# APRS_TRacker_2.net
KiCad netlist of a schematic drawn in EAGLE
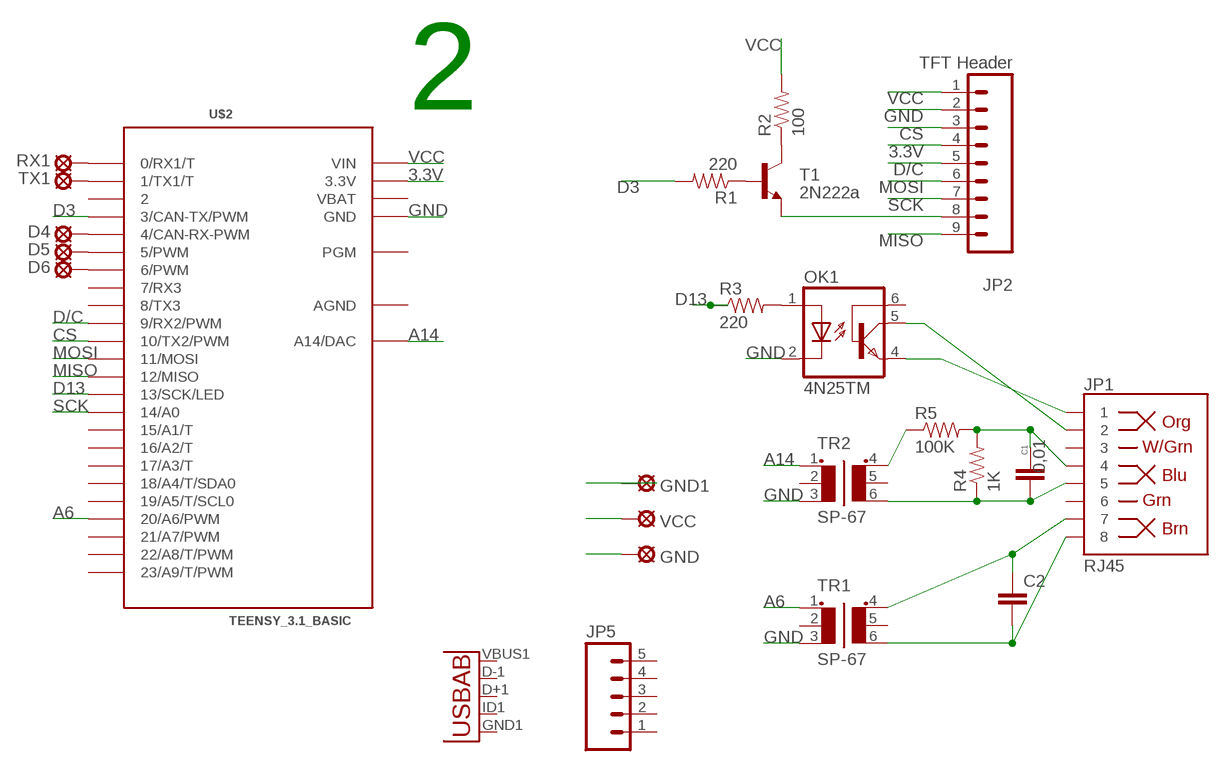
[diagram p0: schematic, sheet 1]

(export (version "E")
  (design (tool "Eeschema 10.0.6"))
  (components
    (comp (ref "C1")
      (value "0,01")
      (footprint "eagle-import:CAP-PTH-SMALL2")
      (libsource (lib "eagle-import") (part "CAPPTH2"))
    )
    (comp (ref "C2")
      (value "CAPPTH2")
      (footprint "eagle-import:CAP-PTH-SMALL2")
      (libsource (lib "eagle-import") (part "CAPPTH2"))
    )
    (comp (ref "D4")
      (value "LSP10")
      (footprint "eagle-import:LSP10")
      (libsource (lib "eagle-import") (part "LSP10"))
    )
    (comp (ref "D5")
      (value "LSP10")
      (footprint "eagle-import:LSP10")
      (libsource (lib "eagle-import") (part "LSP10"))
    )
    (comp (ref "D6")
      (value "LSP10")
      (footprint "eagle-import:LSP10")
      (libsource (lib "eagle-import") (part "LSP10"))
    )
    (comp (ref "GND")
      (value "LSP10")
      (footprint "eagle-import:LSP10")
      (libsource (lib "eagle-import") (part "LSP10"))
    )
    (comp (ref "GND1")
      (value "LSP10")
      (footprint "eagle-import:LSP10")
      (libsource (lib "eagle-import") (part "LSP10"))
    )
    (comp (ref "JP1")
      (value "RJ45")
      (footprint "eagle-import:RJ45-8")
      (libsource (lib "eagle-import") (part "RJ45-8PTH"))
    )
    (comp (ref "JP2")
      (value "TFT Header")
      (footprint "eagle-import:1X09")
      (libsource (lib "eagle-import") (part "M09"))
    )
    (comp (ref "JP5")
      (value "M05PTH")
      (footprint "eagle-import:1X05")
      (libsource (lib "eagle-import") (part "M05PTH"))
    )
    (comp (ref "OK1")
      (value "4N25TM")
      (footprint "eagle-import:DIL6-04")
      (libsource (lib "eagle-import") (part "4N?MT25"))
    )
    (comp (ref "R1")
      (value "220")
      (footprint "eagle-import:AXIAL-0.4")
      (libsource (lib "eagle-import") (part "RESISTORPTH-1/4W"))
    )
    (comp (ref "R2")
      (value "100")
      (footprint "eagle-import:AXIAL-0.4")
      (libsource (lib "eagle-import") (part "RESISTORPTH-1/4W"))
    )
    (comp (ref "R3")
      (value "220")
      (footprint "eagle-import:AXIAL-0.4")
      (libsource (lib "eagle-import") (part "RESISTORPTH-1/4W"))
    )
    (comp (ref "R4")
      (value "1K")
      (footprint "eagle-import:AXIAL-0.4")
      (libsource (lib "eagle-import") (part "RESISTORPTH-1/4W"))
    )
    (comp (ref "R5")
      (value "100K")
      (footprint "eagle-import:AXIAL-0.4")
      (libsource (lib "eagle-import") (part "RESISTORPTH-1/4W"))
    )
    (comp (ref "RX1")
      (value "LSP10")
      (footprint "eagle-import:LSP10")
      (libsource (lib "eagle-import") (part "LSP10"))
    )
    (comp (ref "T1")
      (value "2N222a")
      (footprint "eagle-import:TO-92")
      (libsource (lib "eagle-import") (part "TRANSISTOR_NPNP2N2222A"))
    )
    (comp (ref "TR1")
      (value "SP-67")
      (footprint "eagle-import:SP-67")
      (libsource (lib "eagle-import") (part "SP-67"))
    )
    (comp (ref "TR2")
      (value "SP-67")
      (footprint "eagle-import:SP-67")
      (libsource (lib "eagle-import") (part "SP-67"))
    )
    (comp (ref "TX1")
      (value "LSP10")
      (footprint "eagle-import:LSP10")
      (libsource (lib "eagle-import") (part "LSP10"))
    )
    (comp (ref "U$2")
      (value "TEENSY_3.1_BASIC")
      (footprint "eagle-import:TEENSY_3.1_BASIC")
      (libsource (lib "eagle-import") (part "TEENSY_3.1_BASIC"))
    )
    (comp (ref "U$4")
      (value "USB-AB\"\"")
      (footprint "eagle-import:USB-AB-MICRO-SMD_V02_BOSS")
      (libsource (lib "eagle-import") (part "USB-AB{dblquote}{dblquote}"))
    )
    (comp (ref "VCC")
      (value "LSP10")
      (footprint "eagle-import:LSP10")
      (libsource (lib "eagle-import") (part "LSP10"))
    )
  )
  (nets
    (net (code "1") (name "/3.3V") (class "Default")
      (node (ref "JP2") (pin "4") (pinfunction "4_4") (pintype "passive"))
      (node (ref "U$2") (pin "3.3V") (pinfunction "3.3V_3.3V") (pintype "power_in"))
      (node (ref "U$2") (pin "3.3V1") (pinfunction "3.3V_3.3V1") (pintype "power_in"))
    )
    (net (code "2") (name "/A6") (class "Default")
      (node (ref "TR1") (pin "1") (pinfunction "1_1") (pintype "passive"))
      (node (ref "U$2") (pin "20/A6") (pinfunction "20/A6/PWM_20/A6") (pintype "bidirectional"))
    )
    (net (code "3") (name "/A14") (class "Default")
      (node (ref "TR2") (pin "1") (pinfunction "1_1") (pintype "passive"))
      (node (ref "U$2") (pin "A14") (pinfunction "A14/DAC_A14") (pintype "bidirectional"))
    )
    (net (code "4") (name "/AGND") (class "Default")
      (node (ref "U$2") (pin "AGND") (pinfunction "AGND_AGND") (pintype "power_in"))
    )
    (net (code "5") (name "/CS") (class "Default")
      (node (ref "JP2") (pin "3") (pinfunction "3_3") (pintype "passive"))
      (node (ref "U$2") (pin "10") (pinfunction "10/TX2/PWM_10") (pintype "bidirectional"))
    )
    (net (code "6") (name "/D3") (class "Default")
      (node (ref "R1") (pin "P$2") (pinfunction "2_P$2") (pintype "passive"))
      (node (ref "U$2") (pin "3") (pinfunction "3/CAN-TX/PWM_3") (pintype "bidirectional"))
    )
    (net (code "7") (name "/D13") (class "Default")
      (node (ref "R3") (pin "P$1") (pinfunction "1_P$1") (pintype "passive"))
      (node (ref "U$2") (pin "13") (pinfunction "13/SCK/LED_13") (pintype "bidirectional"))
    )
    (net (code "8") (name "/D{slash}C") (class "Default")
      (node (ref "JP2") (pin "5") (pinfunction "5_5") (pintype "passive"))
      (node (ref "U$2") (pin "9") (pinfunction "9/RX2/PWM_9") (pintype "bidirectional"))
    )
    (net (code "9") (name "/GND") (class "Default")
      (node (ref "GND") (pin "MP") (pinfunction "MP_MP") (pintype "passive"))
      (node (ref "GND1") (pin "MP") (pinfunction "MP_MP") (pintype "passive"))
      (node (ref "JP2") (pin "2") (pinfunction "2_2") (pintype "passive"))
      (node (ref "OK1") (pin "2") (pinfunction "C_2") (pintype "passive"))
      (node (ref "TR1") (pin "3") (pinfunction "3_3") (pintype "passive"))
      (node (ref "TR2") (pin "3") (pinfunction "3_3") (pintype "passive"))
      (node (ref "U$2") (pin "GND") (pinfunction "GND_GND") (pintype "power_in"))
      (node (ref "U$2") (pin "GND1") (pinfunction "GND_GND1") (pintype "power_in"))
    )
    (net (code "10") (name "/MISO") (class "Default")
      (node (ref "JP2") (pin "9") (pinfunction "9_9") (pintype "passive"))
      (node (ref "U$2") (pin "12") (pinfunction "12/MISO_12") (pintype "bidirectional"))
    )
    (net (code "11") (name "/MOSI") (class "Default")
      (node (ref "JP2") (pin "6") (pinfunction "6_6") (pintype "passive"))
      (node (ref "U$2") (pin "11") (pinfunction "11/MOSI_11") (pintype "bidirectional"))
    )
    (net (code "12") (name "/SCK") (class "Default")
      (node (ref "JP2") (pin "7") (pinfunction "7_7") (pintype "passive"))
      (node (ref "U$2") (pin "14/A0") (pinfunction "14/A0_14/A0") (pintype "bidirectional"))
    )
    (net (code "13") (name "/VBAT") (class "Default")
      (node (ref "U$2") (pin "VBAT") (pinfunction "VBAT_VBAT") (pintype "power_in"))
    )
    (net (code "14") (name "/VCC") (class "Default")
      (node (ref "JP2") (pin "1") (pinfunction "1_1") (pintype "passive"))
      (node (ref "R2") (pin "P$2") (pinfunction "2_P$2") (pintype "passive"))
      (node (ref "U$2") (pin "VIN") (pinfunction "VIN_VIN") (pintype "power_in"))
      (node (ref "VCC") (pin "MP") (pinfunction "MP_MP") (pintype "passive"))
    )
    (net (code "15") (name "Net-(C2-Pad1)") (class "Default")
      (node (ref "C2") (pin "1") (pinfunction "1_1") (pintype "passive"))
      (node (ref "JP1") (pin "7") (pinfunction "7_7") (pintype "bidirectional"))
      (node (ref "TR1") (pin "4") (pinfunction "4_4") (pintype "passive"))
    )
    (net (code "16") (name "Net-(C2-Pad2)") (class "Default")
      (node (ref "C2") (pin "2") (pinfunction "2_2") (pintype "passive"))
      (node (ref "JP1") (pin "8") (pinfunction "8_8") (pintype "bidirectional"))
      (node (ref "TR1") (pin "6") (pinfunction "6_6") (pintype "passive"))
    )
    (net (code "17") (name "Net-(OK1-A)") (class "Default")
      (node (ref "OK1") (pin "1") (pinfunction "A_1") (pintype "passive"))
      (node (ref "R3") (pin "P$2") (pinfunction "2_P$2") (pintype "passive"))
    )
    (net (code "18") (name "Net-(OK1-COL)") (class "Default")
      (node (ref "JP1") (pin "2") (pinfunction "2_2") (pintype "bidirectional"))
      (node (ref "OK1") (pin "5") (pinfunction "COL_5") (pintype "passive"))
    )
    (net (code "19") (name "Net-(OK1-EMI)") (class "Default")
      (node (ref "JP1") (pin "1") (pinfunction "1_1") (pintype "bidirectional"))
      (node (ref "OK1") (pin "4") (pinfunction "EMI_4") (pintype "passive"))
    )
    (net (code "20") (name "Net-(R1-1)") (class "Default")
      (node (ref "R1") (pin "P$1") (pinfunction "1_P$1") (pintype "passive"))
      (node (ref "T1") (pin "2") (pinfunction "B_2") (pintype "passive"))
    )
    (net (code "21") (name "Net-(R2-1)") (class "Default")
      (node (ref "R2") (pin "P$1") (pinfunction "1_P$1") (pintype "passive"))
      (node (ref "T1") (pin "1") (pinfunction "C_1") (pintype "passive"))
    )
    (net (code "22") (name "Net-(R4-1)") (class "Default")
      (node (ref "C1") (pin "2") (pinfunction "2_2") (pintype "passive"))
      (node (ref "JP1") (pin "5") (pinfunction "5_5") (pintype "bidirectional"))
      (node (ref "R4") (pin "P$1") (pinfunction "1_P$1") (pintype "passive"))
      (node (ref "TR2") (pin "6") (pinfunction "6_6") (pintype "passive"))
    )
    (net (code "23") (name "Net-(R4-2)") (class "Default")
      (node (ref "C1") (pin "1") (pinfunction "1_1") (pintype "passive"))
      (node (ref "JP1") (pin "4") (pinfunction "4_4") (pintype "bidirectional"))
      (node (ref "R4") (pin "P$2") (pinfunction "2_P$2") (pintype "passive"))
      (node (ref "R5") (pin "P$2") (pinfunction "2_P$2") (pintype "passive"))
    )
    (net (code "24") (name "Net-(R5-1)") (class "Default")
      (node (ref "R5") (pin "P$1") (pinfunction "1_P$1") (pintype "passive"))
      (node (ref "TR2") (pin "4") (pinfunction "4_4") (pintype "passive"))
    )
    (net (code "25") (name "Net-(T1-E)") (class "Default")
      (node (ref "JP2") (pin "8") (pinfunction "8_8") (pintype "passive"))
      (node (ref "T1") (pin "3") (pinfunction "E_3") (pintype "passive"))
    )
    (net (code "26") (name "Net-(U$2-0{slash}RX1{slash}T)") (class "Default")
      (node (ref "RX1") (pin "MP") (pinfunction "MP_MP") (pintype "passive"))
      (node (ref "U$2") (pin "0") (pinfunction "0/RX1/T_0") (pintype "bidirectional"))
    )
    (net (code "27") (name "Net-(U$2-1{slash}TX1{slash}T)") (class "Default")
      (node (ref "TX1") (pin "MP") (pinfunction "MP_MP") (pintype "passive"))
      (node (ref "U$2") (pin "1") (pinfunction "1/TX1/T_1") (pintype "bidirectional"))
    )
    (net (code "28") (name "Net-(U$2-4{slash}CAN-RX-PWM)") (class "Default")
      (node (ref "D4") (pin "MP") (pinfunction "MP_MP") (pintype "passive"))
      (node (ref "U$2") (pin "4") (pinfunction "4/CAN-RX-PWM_4") (pintype "bidirectional"))
    )
    (net (code "29") (name "Net-(U$2-5{slash}PWM)") (class "Default")
      (node (ref "D5") (pin "MP") (pinfunction "MP_MP") (pintype "passive"))
      (node (ref "U$2") (pin "5") (pinfunction "5/PWM_5") (pintype "bidirectional"))
    )
    (net (code "30") (name "Net-(U$2-6{slash}PWM)") (class "Default")
      (node (ref "D6") (pin "MP") (pinfunction "MP_MP") (pintype "passive"))
      (node (ref "U$2") (pin "6") (pinfunction "6/PWM_6") (pintype "bidirectional"))
    )
    (net (code "31") (name "unconnected-(JP1-Pad3)") (class "Default")
      (node (ref "JP1") (pin "3") (pinfunction "3_3") (pintype "bidirectional"))
    )
    (net (code "32") (name "unconnected-(JP1-Pad6)") (class "Default")
      (node (ref "JP1") (pin "6") (pinfunction "6_6") (pintype "bidirectional"))
    )
    (net (code "33") (name "unconnected-(JP5-Pad1)") (class "Default")
      (node (ref "JP5") (pin "1") (pinfunction "1_1") (pintype "passive"))
    )
    (net (code "34") (name "unconnected-(JP5-Pad2)") (class "Default")
      (node (ref "JP5") (pin "2") (pinfunction "2_2") (pintype "passive"))
    )
    (net (code "35") (name "unconnected-(JP5-Pad3)") (class "Default")
      (node (ref "JP5") (pin "3") (pinfunction "3_3") (pintype "passive"))
    )
    (net (code "36") (name "unconnected-(JP5-Pad4)") (class "Default")
      (node (ref "JP5") (pin "4") (pinfunction "4_4") (pintype "passive"))
    )
    (net (code "37") (name "unconnected-(JP5-Pad5)") (class "Default")
      (node (ref "JP5") (pin "5") (pinfunction "5_5") (pintype "passive"))
    )
    (net (code "38") (name "unconnected-(OK1-BAS-Pad6)") (class "Default")
      (node (ref "OK1") (pin "6") (pinfunction "BAS_6") (pintype "passive"))
    )
    (net (code "39") (name "unconnected-(TR1-Pad2)") (class "Default")
      (node (ref "TR1") (pin "2") (pinfunction "2_2") (pintype "passive"))
    )
    (net (code "40") (name "unconnected-(TR1-Pad5)") (class "Default")
      (node (ref "TR1") (pin "5") (pinfunction "5_5") (pintype "passive"))
    )
    (net (code "41") (name "unconnected-(TR2-Pad2)") (class "Default")
      (node (ref "TR2") (pin "2") (pinfunction "2_2") (pintype "passive"))
    )
    (net (code "42") (name "unconnected-(TR2-Pad5)") (class "Default")
      (node (ref "TR2") (pin "5") (pinfunction "5_5") (pintype "passive"))
    )
    (net (code "43") (name "unconnected-(U$2-7{slash}RX3-Pad7)") (class "Default")
      (node (ref "U$2") (pin "7") (pinfunction "7/RX3_7") (pintype "bidirectional"))
    )
    (net (code "44") (name "unconnected-(U$2-8{slash}TX3-Pad8)") (class "Default")
      (node (ref "U$2") (pin "8") (pinfunction "8/TX3_8") (pintype "bidirectional"))
    )
    (net (code "45") (name "unconnected-(U$2-15{slash}A1{slash}T-Pad15{slash}A1)") (class "Default")
      (node (ref "U$2") (pin "15/A1") (pinfunction "15/A1/T_15/A1") (pintype "bidirectional"))
    )
    (net (code "46") (name "unconnected-(U$2-16{slash}A2{slash}T-Pad16{slash}A2)") (class "Default")
      (node (ref "U$2") (pin "16/A2") (pinfunction "16/A2/T_16/A2") (pintype "bidirectional"))
    )
    (net (code "47") (name "unconnected-(U$2-17{slash}A3{slash}T-Pad17{slash}A3)") (class "Default")
      (node (ref "U$2") (pin "17/A3") (pinfunction "17/A3/T_17/A3") (pintype "bidirectional"))
    )
    (net (code "48") (name "unconnected-(U$2-18{slash}A4{slash}T{slash}SDA0-Pad18{slash}A4)") (class "Default")
      (node (ref "U$2") (pin "18/A4") (pinfunction "18/A4/T/SDA0_18/A4") (pintype "bidirectional"))
    )
    (net (code "49") (name "unconnected-(U$2-19{slash}A5{slash}T{slash}SCL0-Pad19{slash}A5)") (class "Default")
      (node (ref "U$2") (pin "19/A5") (pinfunction "19/A5/T/SCL0_19/A5") (pintype "bidirectional"))
    )
    (net (code "50") (name "unconnected-(U$2-21{slash}A7{slash}PWM-Pad21{slash}A7)") (class "Default")
      (node (ref "U$2") (pin "21/A7") (pinfunction "21/A7/PWM_21/A7") (pintype "bidirectional"))
    )
    (net (code "51") (name "unconnected-(U$2-22{slash}A8{slash}T{slash}PWM-Pad22{slash}A8)") (class "Default")
      (node (ref "U$2") (pin "22/A8") (pinfunction "22/A8/T/PWM_22/A8") (pintype "bidirectional"))
    )
    (net (code "52") (name "unconnected-(U$2-23{slash}A9{slash}T{slash}PWM-Pad23{slash}A9)") (class "Default")
      (node (ref "U$2") (pin "23/A9") (pinfunction "23/A9/T/PWM_23/A9") (pintype "bidirectional"))
    )
    (net (code "53") (name "unconnected-(U$2-Pad2)") (class "Default")
      (node (ref "U$2") (pin "2") (pinfunction "2_2") (pintype "bidirectional"))
    )
    (net (code "54") (name "unconnected-(U$2-PadPGM)") (class "Default")
      (node (ref "U$2") (pin "PGM") (pinfunction "PGM_PGM") (pintype "bidirectional"))
    )
    (net (code "55") (name "unconnected-(U$4-D+-PadD+1)") (class "Default")
      (node (ref "U$4") (pin "D+1") (pinfunction "D+_D+1") (pintype "bidirectional"))
    )
    (net (code "56") (name "unconnected-(U$4-D--PadD-1)") (class "Default")
      (node (ref "U$4") (pin "D-1") (pinfunction "D-_D-1") (pintype "bidirectional"))
    )
    (net (code "57") (name "unconnected-(U$4-GND-PadGND1)") (class "Default")
      (node (ref "U$4") (pin "GND1") (pinfunction "GND_GND1") (pintype "bidirectional"))
    )
    (net (code "58") (name "unconnected-(U$4-USBID-PadID1)") (class "Default")
      (node (ref "U$4") (pin "ID1") (pinfunction "USBID_ID1") (pintype "bidirectional"))
    )
    (net (code "59") (name "unconnected-(U$4-VBUS-PadVBUS1)") (class "Default")
      (node (ref "U$4") (pin "VBUS1") (pinfunction "VBUS_VBUS1") (pintype "bidirectional"))
    )
  )
)
